# boomerangv2.net
KiCad netlist of a schematic drawn in EAGLE
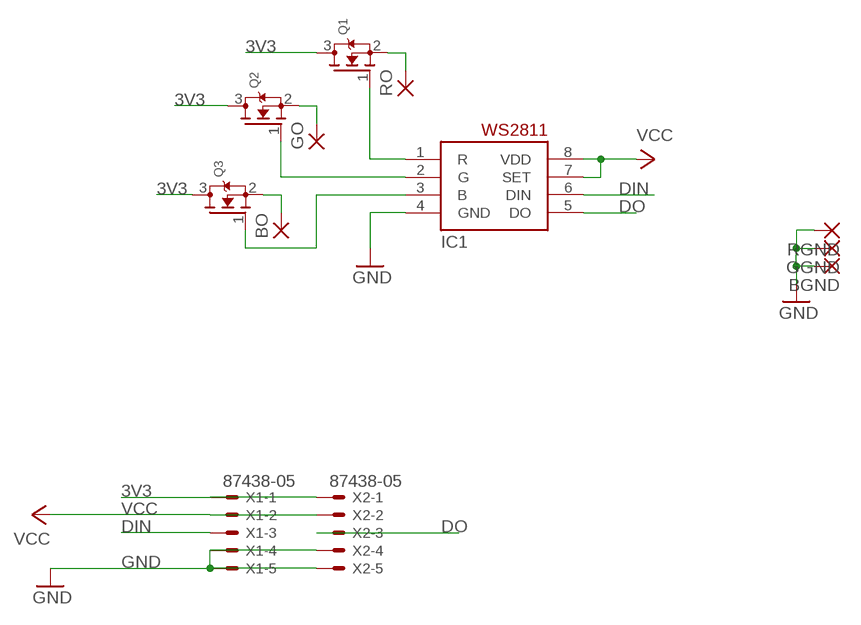
[diagram p0: schematic, sheet 1]

(export (version "E")
  (design (tool "Eeschema 10.0.6"))
  (components
    (comp (ref "BGND")
      (value "SMD2")
      (footprint "eagle-import:SMD1,27-2,54")
      (libsource (lib "eagle-import") (part "SMD2"))
    )
    (comp (ref "BO")
      (value "SMD2")
      (footprint "eagle-import:SMD1,27-2,54")
      (libsource (lib "eagle-import") (part "SMD2"))
    )
    (comp (ref "GGND")
      (value "SMD2")
      (footprint "eagle-import:SMD1,27-2,54")
      (libsource (lib "eagle-import") (part "SMD2"))
    )
    (comp (ref "GO")
      (value "SMD2")
      (footprint "eagle-import:SMD1,27-2,54")
      (libsource (lib "eagle-import") (part "SMD2"))
    )
    (comp (ref "IC1")
      (value "WS2811-SOP8")
      (footprint "eagle-import:SO08-SKINNYPADS")
      (libsource (lib "eagle-import") (part "WS2811-SOP8"))
    )
    (comp (ref "Q1")
      (value "MOSFET-NREFLOW")
      (footprint "eagle-import:SOT23")
      (libsource (lib "eagle-import") (part "MOSFET-NREFLOW"))
    )
    (comp (ref "Q2")
      (value "MOSFET-NREFLOW")
      (footprint "eagle-import:SOT23")
      (libsource (lib "eagle-import") (part "MOSFET-NREFLOW"))
    )
    (comp (ref "Q3")
      (value "MOSFET-NREFLOW")
      (footprint "eagle-import:SOT23")
      (libsource (lib "eagle-import") (part "MOSFET-NREFLOW"))
    )
    (comp (ref "RGND")
      (value "SMD2")
      (footprint "eagle-import:SMD1,27-2,54")
      (libsource (lib "eagle-import") (part "SMD2"))
    )
    (comp (ref "RO")
      (value "SMD2")
      (footprint "eagle-import:SMD1,27-2,54")
      (libsource (lib "eagle-import") (part "SMD2"))
    )
    (comp (ref "X1")
      (value "87438-05")
      (footprint "eagle-import:87438-05")
      (fields (field (name "MPN") "87438-0542"))
      (libsource (lib "eagle-import") (part "87438-05"))
    )
    (comp (ref "X2")
      (value "87438-05")
      (footprint "eagle-import:87438-05")
      (fields (field (name "MPN") "87438-0542"))
      (libsource (lib "eagle-import") (part "87438-05"))
    )
  )
  (nets
    (net (code "1") (name "/3V3") (class "Default")
      (node (ref "Q1") (pin "3") (pinfunction "D_3") (pintype "bidirectional"))
      (node (ref "Q2") (pin "3") (pinfunction "D_3") (pintype "bidirectional"))
      (node (ref "Q3") (pin "3") (pinfunction "D_3") (pintype "bidirectional"))
      (node (ref "X1") (pin "1") (pinfunction "S_1") (pintype "passive"))
      (node (ref "X2") (pin "1") (pinfunction "S_1") (pintype "passive"))
    )
    (net (code "2") (name "/DIN") (class "Default")
      (node (ref "IC1") (pin "6") (pinfunction "DIN_6") (pintype "input"))
      (node (ref "X1") (pin "3") (pinfunction "S_3") (pintype "passive"))
    )
    (net (code "3") (name "/DO") (class "Default")
      (node (ref "IC1") (pin "5") (pinfunction "DO_5") (pintype "output"))
      (node (ref "X2") (pin "3") (pinfunction "S_3") (pintype "passive"))
    )
    (net (code "4") (name "GND") (class "Default")
      (node (ref "BGND") (pin "1") (pinfunction "P_1") (pintype "passive"))
      (node (ref "GGND") (pin "1") (pinfunction "P_1") (pintype "passive"))
      (node (ref "IC1") (pin "4") (pinfunction "GND_4") (pintype "power_in"))
      (node (ref "RGND") (pin "1") (pinfunction "P_1") (pintype "passive"))
      (node (ref "X1") (pin "4") (pinfunction "S_4") (pintype "passive"))
      (node (ref "X1") (pin "5") (pinfunction "S_5") (pintype "passive"))
      (node (ref "X2") (pin "4") (pinfunction "S_4") (pintype "passive"))
      (node (ref "X2") (pin "5") (pinfunction "S_5") (pintype "passive"))
    )
    (net (code "5") (name "Net-(BO-P)") (class "Default")
      (node (ref "BO") (pin "1") (pinfunction "P_1") (pintype "passive"))
      (node (ref "Q3") (pin "2") (pinfunction "S_2") (pintype "bidirectional"))
    )
    (net (code "6") (name "Net-(GO-P)") (class "Default")
      (node (ref "GO") (pin "1") (pinfunction "P_1") (pintype "passive"))
      (node (ref "Q2") (pin "2") (pinfunction "S_2") (pintype "bidirectional"))
    )
    (net (code "7") (name "Net-(IC1-B)") (class "Default")
      (node (ref "IC1") (pin "3") (pinfunction "B_3") (pintype "open_collector"))
      (node (ref "Q3") (pin "1") (pinfunction "G_1") (pintype "bidirectional"))
    )
    (net (code "8") (name "Net-(IC1-G)") (class "Default")
      (node (ref "IC1") (pin "2") (pinfunction "G_2") (pintype "open_collector"))
      (node (ref "Q2") (pin "1") (pinfunction "G_1") (pintype "bidirectional"))
    )
    (net (code "9") (name "Net-(IC1-R)") (class "Default")
      (node (ref "IC1") (pin "1") (pinfunction "R_1") (pintype "open_collector"))
      (node (ref "Q1") (pin "1") (pinfunction "G_1") (pintype "bidirectional"))
    )
    (net (code "10") (name "Net-(Q1-S)") (class "Default")
      (node (ref "Q1") (pin "2") (pinfunction "S_2") (pintype "bidirectional"))
      (node (ref "RO") (pin "1") (pinfunction "P_1") (pintype "passive"))
    )
    (net (code "11") (name "VCC") (class "Default")
      (node (ref "IC1") (pin "7") (pinfunction "SET_7") (pintype "input"))
      (node (ref "IC1") (pin "8") (pinfunction "VDD_8") (pintype "power_in"))
      (node (ref "X1") (pin "2") (pinfunction "S_2") (pintype "passive"))
      (node (ref "X2") (pin "2") (pinfunction "S_2") (pintype "passive"))
    )
  )
)
